# ESP32-Proto2-OSHPARK.net
KiCad netlist of a schematic drawn in EAGLE
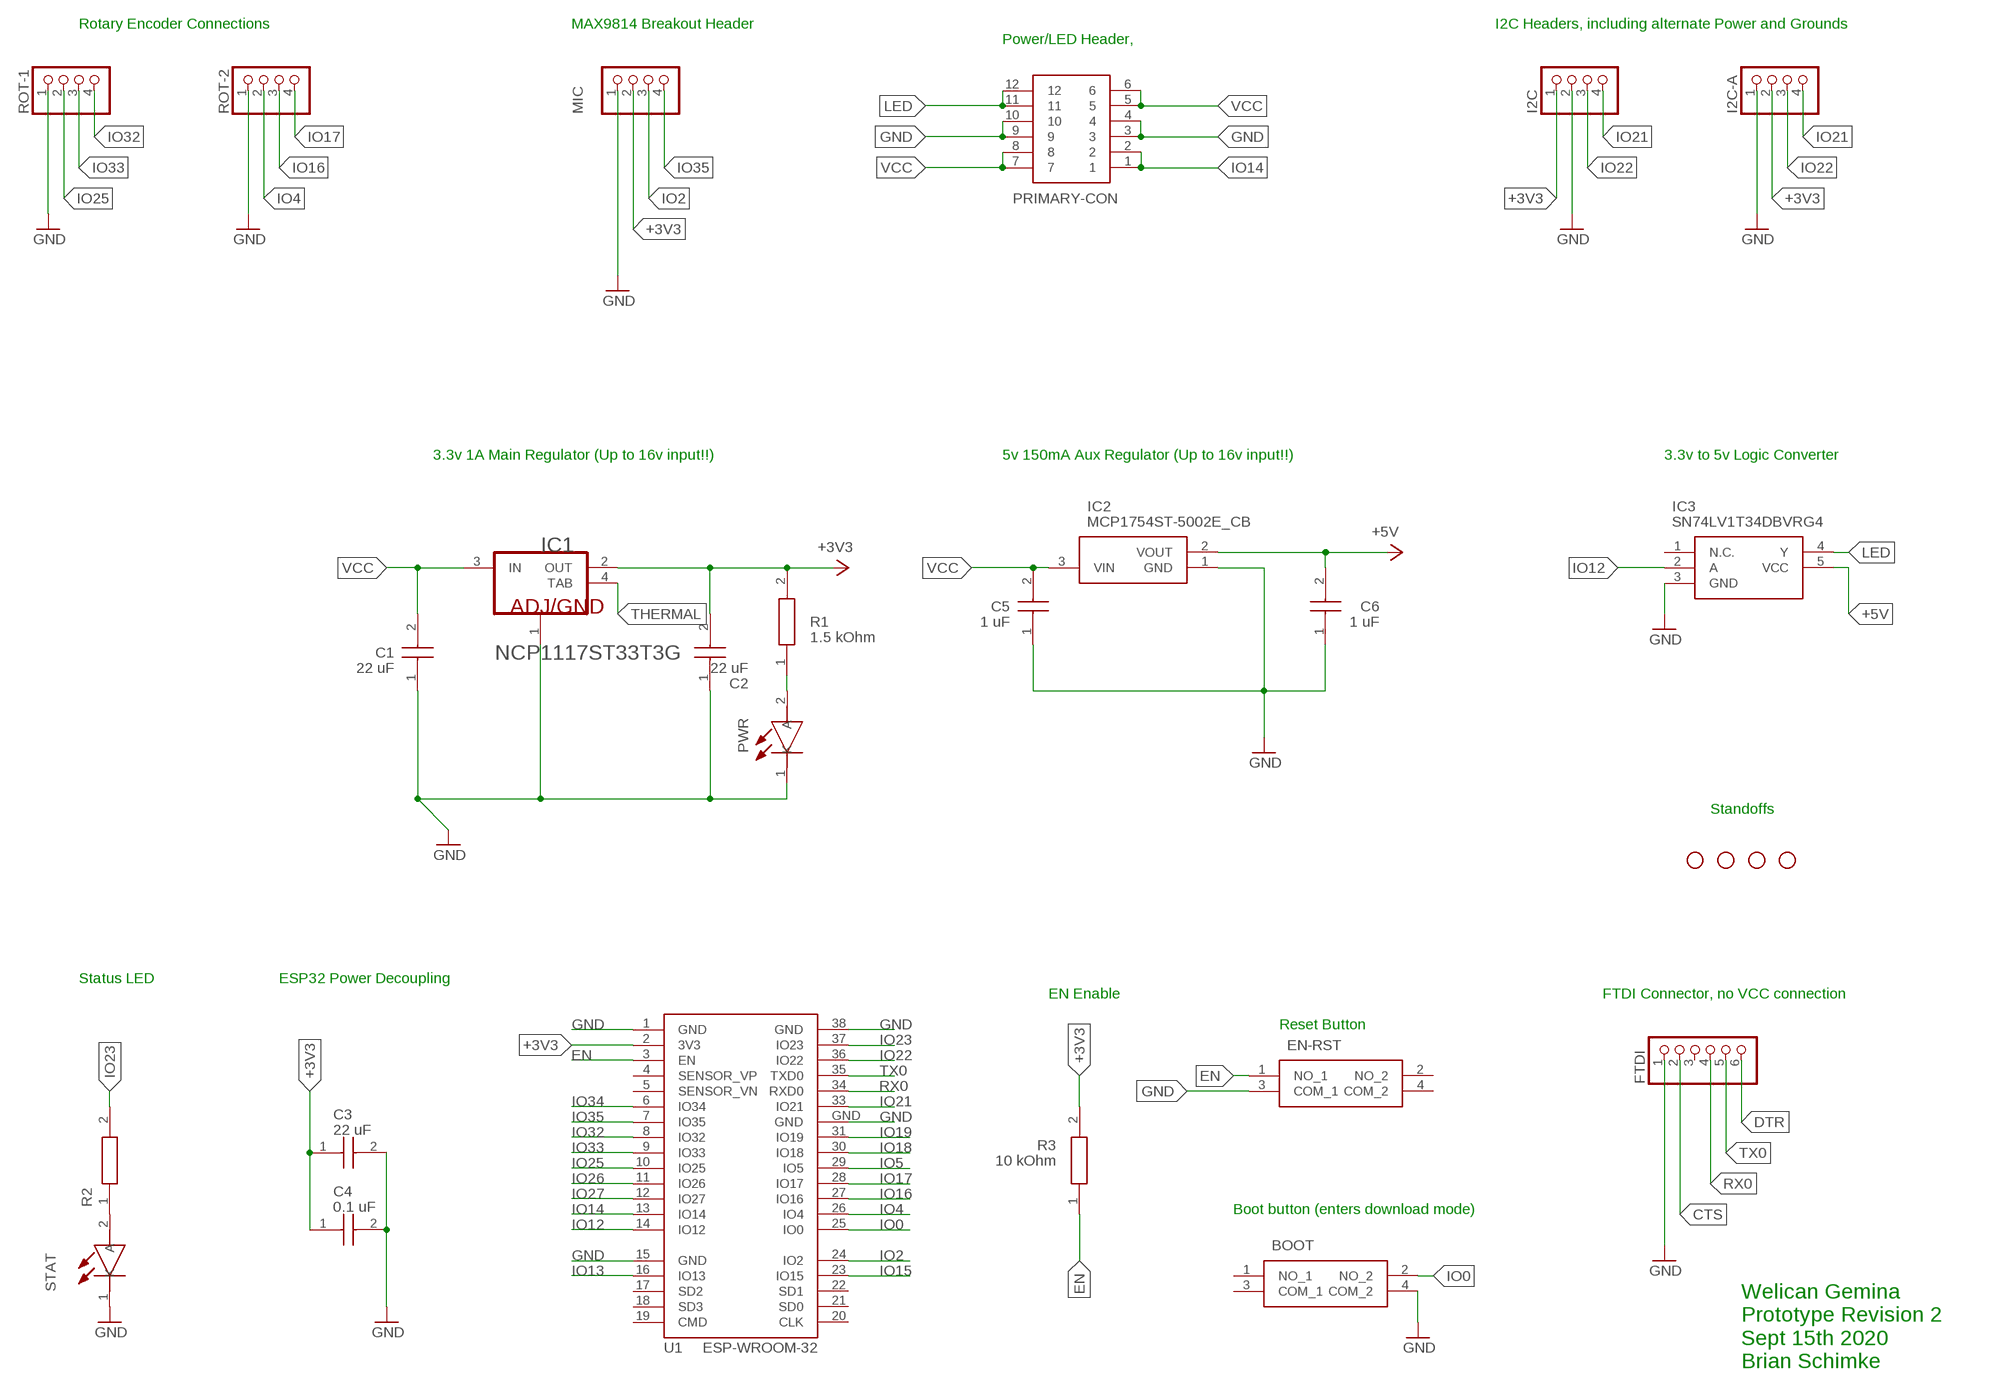
[diagram p0: schematic, sheet 1]

(export (version "E")
  (design (tool "Eeschema 10.0.6"))
  (components
    (comp (ref "BOOT")
      (value "PTS647SK70SMTR2LFS")
      (footprint "eagle-import:PTS647SK70SMTR2LFS")
      (fields (field (name "MOUSER_PART_NUMBER") "611-PTS647SK70SMTR2L"))
      (libsource (lib "eagle-import") (part "PTS647SK70SMTR2LFS"))
    )
    (comp (ref "C1")
      (value "22 uF")
      (footprint "eagle-import:CAPC3216X180N")
      (fields
        (field (name "MANUFACTURER_PART_NUMBER") "C1206C226M4PACTU")
        (field (name "MOUSER_PART_NUMBER") "80-C1206C226M4P")
      )
      (libsource (lib "eagle-import") (part "C1206C226M4PACTU"))
    )
    (comp (ref "C2")
      (value "22 uF")
      (footprint "eagle-import:CAPC3216X180N")
      (fields
        (field (name "MANUFACTURER_PART_NUMBER") "C1206C226M4PACTU")
        (field (name "MOUSER_PART_NUMBER") "80-C1206C226M4P")
      )
      (libsource (lib "eagle-import") (part "C1206C226M4PACTU"))
    )
    (comp (ref "C3")
      (value "22 uF")
      (footprint "eagle-import:CAPC3216X180N")
      (fields
        (field (name "MANUFACTURER_PART_NUMBER") "C1206C226M4PACTU")
        (field (name "MOUSER_PART_NUMBER") "80-C1206C226M4P")
      )
      (libsource (lib "eagle-import") (part "C1206C226M4PACTU"))
    )
    (comp (ref "C4")
      (value "0.1 uF")
      (footprint "eagle-import:CAPC3216X180N")
      (fields
        (field (name "MANUFACTURER_PART_NUMBER") "C1206C226M4PACTU")
        (field (name "MOUSER_PART_NUMBER") "80-C1206C226M4P")
      )
      (libsource (lib "eagle-import") (part "C1206C226M4PACTU"))
    )
    (comp (ref "C5")
      (value "1 uF")
      (footprint "eagle-import:CAPC3216X180N")
      (fields
        (field (name "MANUFACTURER_PART_NUMBER") "C1206C226M4PACTU")
        (field (name "MOUSER_PART_NUMBER") "80-C1206C226M4P")
      )
      (libsource (lib "eagle-import") (part "C1206C226M4PACTU"))
    )
    (comp (ref "C6")
      (value "1 uF")
      (footprint "eagle-import:CAPC3216X180N")
      (fields
        (field (name "MANUFACTURER_PART_NUMBER") "C1206C226M4PACTU")
        (field (name "MOUSER_PART_NUMBER") "80-C1206C226M4P")
      )
      (libsource (lib "eagle-import") (part "C1206C226M4PACTU"))
    )
    (comp (ref "EN-RST")
      (value "PTS647SK70SMTR2LFS")
      (footprint "eagle-import:PTS647SK70SMTR2LFS")
      (fields (field (name "MOUSER_PART_NUMBER") "611-PTS647SK70SMTR2L"))
      (libsource (lib "eagle-import") (part "PTS647SK70SMTR2LFS"))
    )
    (comp (ref "FTDI")
      (value "PINHD-1X6")
      (footprint "eagle-import:1X06")
      (libsource (lib "eagle-import") (part "PINHD-1X6"))
    )
    (comp (ref "H1")
      (value "STAND-OFF")
      (footprint "eagle-import:STAND-OFF")
      (libsource (lib "eagle-import") (part "STAND-OFF"))
    )
    (comp (ref "H2")
      (value "STAND-OFF")
      (footprint "eagle-import:STAND-OFF")
      (libsource (lib "eagle-import") (part "STAND-OFF"))
    )
    (comp (ref "H3")
      (value "STAND-OFF")
      (footprint "eagle-import:STAND-OFF")
      (libsource (lib "eagle-import") (part "STAND-OFF"))
    )
    (comp (ref "H4")
      (value "STAND-OFF")
      (footprint "eagle-import:STAND-OFF")
      (libsource (lib "eagle-import") (part "STAND-OFF"))
    )
    (comp (ref "I2C")
      (value "PINHD-1X4")
      (footprint "eagle-import:1X04")
      (libsource (lib "eagle-import") (part "PINHD-1X4"))
    )
    (comp (ref "I2C-A")
      (value "PINHD-1X4")
      (footprint "eagle-import:1X04")
      (libsource (lib "eagle-import") (part "PINHD-1X4"))
    )
    (comp (ref "IC1")
      (value "ON_SEMICONDUCTOR_NCP1117ST33T3GON_SEMICONDUCTOR_NCP1117ST33T3G_0_0")
      (footprint "eagle-import:ON_SEMICONDUCTOR_NCP1117ST33T3G_0")
      (fields
        (field (name "MF") "ON Semiconductor")
        (field (name "MPN") "NCP1117ST33T3G")
        (field (name "TOLERANCE") "1%")
      )
      (libsource (lib "eagle-import") (part "ON_SEMICONDUCTOR_NCP1117ST33T3GON_SEMICONDUCTOR_NCP1117ST33T3G_0_0"))
    )
    (comp (ref "IC2")
      (value "MCP1754ST-5002E_CB")
      (footprint "eagle-import:SOT95P255X145-3N")
      (fields
        (field (name "MANUFACTURER_PART_NUMBER") "MCP1754ST-5002E/CB")
        (field (name "MOUSER_PART_NUMBER") "579-MCP1754T-5002ECB")
      )
      (libsource (lib "eagle-import") (part "MCP1754ST-5002E_CB"))
    )
    (comp (ref "IC3")
      (value "SN74LV1T34DBVRG4")
      (footprint "eagle-import:SOT95P280X145-5N")
      (fields (field (name "MOUSER_PART_NUMBER") "595-SN74LV1T34DBVRG4"))
      (libsource (lib "eagle-import") (part "SN74LV1T34DBVRG4"))
    )
    (comp (ref "MIC")
      (value "PINHD-1X4")
      (footprint "eagle-import:1X04")
      (libsource (lib "eagle-import") (part "PINHD-1X4"))
    )
    (comp (ref "PRIMARY-CON")
      (value "1-2834015-6")
      (footprint "eagle-import:SHDR12W90P508X254_2X6_1824X128")
      (fields (field (name "MOUSER_PART_NUMBER") "571-1-2834015-6"))
      (libsource (lib "eagle-import") (part "1-2834015-6"))
    )
    (comp (ref "PWR")
      (value "150120AS75000")
      (footprint "eagle-import:LEDSC320X160X78-2N")
      (fields (field (name "MOUSER_PART_NUMBER") "710-150120AS75000"))
      (libsource (lib "eagle-import") (part "150120AS75000"))
    )
    (comp (ref "R1")
      (value "1.5 kOhm")
      (footprint "eagle-import:RESC3216X60N")
      (fields
        (field (name "MANUFACTURER_PART_NUMBER") "CRCW12061K00FKEB")
        (field (name "MOUSER_PART_NUMBER") "71-CRCW12061K00FKEB")
      )
      (libsource (lib "eagle-import") (part "CRCW12061K00FKEB"))
    )
    (comp (ref "R2")
      (value "CRCW12061K00FKEB")
      (footprint "eagle-import:RESC3216X60N")
      (fields (field (name "MOUSER_PART_NUMBER") "71-CRCW12061K00FKEB"))
      (libsource (lib "eagle-import") (part "CRCW12061K00FKEB"))
    )
    (comp (ref "R3")
      (value "10 kOhm")
      (footprint "eagle-import:RESC3216X60N")
      (fields
        (field (name "MANUFACTURER_PART_NUMBER") "CRCW12061K00FKEB")
        (field (name "MOUSER_PART_NUMBER") "71-CRCW12061K00FKEB")
      )
      (libsource (lib "eagle-import") (part "CRCW12061K00FKEB"))
    )
    (comp (ref "ROT-1")
      (value "PINHD-1X4")
      (footprint "eagle-import:1X04")
      (libsource (lib "eagle-import") (part "PINHD-1X4"))
    )
    (comp (ref "ROT-2")
      (value "PINHD-1X4")
      (footprint "eagle-import:1X04")
      (libsource (lib "eagle-import") (part "PINHD-1X4"))
    )
    (comp (ref "STAT")
      (value "150120AS75000")
      (footprint "eagle-import:LEDSC320X160X78-2N")
      (fields (field (name "MOUSER_PART_NUMBER") "710-150120AS75000"))
      (libsource (lib "eagle-import") (part "150120AS75000"))
    )
    (comp (ref "U1")
      (value "ESP-WROOM-32")
      (footprint "eagle-import:ESP-WROOM-32")
      (libsource (lib "eagle-import") (part "ESP-WROOM-32"))
    )
  )
  (nets
    (net (code "1") (name "+3V3") (class "Default")
      (node (ref "C2") (pin "2") (pinfunction "2_2") (pintype "bidirectional"))
      (node (ref "C3") (pin "1") (pinfunction "1_1") (pintype "bidirectional"))
      (node (ref "C4") (pin "1") (pinfunction "1_1") (pintype "bidirectional"))
      (node (ref "I2C") (pin "1") (pinfunction "1_1") (pintype "passive"))
      (node (ref "I2C-A") (pin "2") (pinfunction "2_2") (pintype "passive"))
      (node (ref "IC1") (pin "2") (pinfunction "OUT_2") (pintype "power_in"))
      (node (ref "MIC") (pin "2") (pinfunction "2_2") (pintype "passive"))
      (node (ref "R1") (pin "2") (pinfunction "2_2") (pintype "bidirectional"))
      (node (ref "R3") (pin "2") (pinfunction "2_2") (pintype "bidirectional"))
      (node (ref "U1") (pin "2") (pinfunction "3V3_2") (pintype "power_in"))
    )
    (net (code "2") (name "+5V") (class "Default")
      (node (ref "C6") (pin "2") (pinfunction "2_2") (pintype "bidirectional"))
      (node (ref "IC2") (pin "2") (pinfunction "VOUT_2") (pintype "bidirectional"))
      (node (ref "IC3") (pin "5") (pinfunction "VCC_5") (pintype "bidirectional"))
    )
    (net (code "3") (name "/IO5") (class "Default")
      (node (ref "U1") (pin "29") (pinfunction "IO5_29") (pintype "bidirectional"))
    )
    (net (code "4") (name "/IO13") (class "Default")
      (node (ref "U1") (pin "16") (pinfunction "IO13_16") (pintype "bidirectional"))
    )
    (net (code "5") (name "/IO15") (class "Default")
      (node (ref "U1") (pin "23") (pinfunction "IO15_23") (pintype "bidirectional"))
    )
    (net (code "6") (name "/IO18") (class "Default")
      (node (ref "U1") (pin "30") (pinfunction "IO18_30") (pintype "bidirectional"))
    )
    (net (code "7") (name "/IO19") (class "Default")
      (node (ref "U1") (pin "31") (pinfunction "IO19_31") (pintype "bidirectional"))
    )
    (net (code "8") (name "/IO26") (class "Default")
      (node (ref "U1") (pin "11") (pinfunction "IO26_11") (pintype "bidirectional"))
    )
    (net (code "9") (name "/IO27") (class "Default")
      (node (ref "U1") (pin "12") (pinfunction "IO27_12") (pintype "bidirectional"))
    )
    (net (code "10") (name "/IO34") (class "Default")
      (node (ref "U1") (pin "6") (pinfunction "IO34_6") (pintype "bidirectional"))
    )
    (net (code "11") (name "CTS") (class "Default")
      (node (ref "FTDI") (pin "2") (pinfunction "2_2") (pintype "passive"))
    )
    (net (code "12") (name "DTR") (class "Default")
      (node (ref "FTDI") (pin "6") (pinfunction "6_6") (pintype "passive"))
    )
    (net (code "13") (name "EN") (class "Default")
      (node (ref "EN-RST") (pin "1") (pinfunction "NO_1_1") (pintype "bidirectional"))
      (node (ref "R3") (pin "1") (pinfunction "1_1") (pintype "bidirectional"))
      (node (ref "U1") (pin "3") (pinfunction "EN_3") (pintype "input"))
    )
    (net (code "14") (name "GND") (class "Default")
      (node (ref "BOOT") (pin "4") (pinfunction "COM_2_4") (pintype "bidirectional"))
      (node (ref "C1") (pin "1") (pinfunction "1_1") (pintype "bidirectional"))
      (node (ref "C2") (pin "1") (pinfunction "1_1") (pintype "bidirectional"))
      (node (ref "C3") (pin "2") (pinfunction "2_2") (pintype "bidirectional"))
      (node (ref "C4") (pin "2") (pinfunction "2_2") (pintype "bidirectional"))
      (node (ref "C5") (pin "1") (pinfunction "1_1") (pintype "bidirectional"))
      (node (ref "C6") (pin "1") (pinfunction "1_1") (pintype "bidirectional"))
      (node (ref "EN-RST") (pin "3") (pinfunction "COM_1_3") (pintype "bidirectional"))
      (node (ref "FTDI") (pin "1") (pinfunction "1_1") (pintype "passive"))
      (node (ref "I2C") (pin "2") (pinfunction "2_2") (pintype "passive"))
      (node (ref "I2C-A") (pin "1") (pinfunction "1_1") (pintype "passive"))
      (node (ref "IC1") (pin "1") (pinfunction "ADJ/GND_1") (pintype "passive"))
      (node (ref "IC2") (pin "1") (pinfunction "GND_1") (pintype "bidirectional"))
      (node (ref "IC3") (pin "3") (pinfunction "GND_3") (pintype "bidirectional"))
      (node (ref "MIC") (pin "1") (pinfunction "1_1") (pintype "passive"))
      (node (ref "PRIMARY-CON") (pin "10") (pinfunction "10_10") (pintype "bidirectional"))
      (node (ref "PRIMARY-CON") (pin "3") (pinfunction "3_3") (pintype "bidirectional"))
      (node (ref "PRIMARY-CON") (pin "4") (pinfunction "4_4") (pintype "bidirectional"))
      (node (ref "PRIMARY-CON") (pin "9") (pinfunction "9_9") (pintype "bidirectional"))
      (node (ref "PWR") (pin "1") (pinfunction "K_1") (pintype "bidirectional"))
      (node (ref "ROT-1") (pin "1") (pinfunction "1_1") (pintype "passive"))
      (node (ref "ROT-2") (pin "1") (pinfunction "1_1") (pintype "passive"))
      (node (ref "STAT") (pin "1") (pinfunction "K_1") (pintype "bidirectional"))
      (node (ref "U1") (pin "1") (pinfunction "GND_1") (pintype "power_in"))
      (node (ref "U1") (pin "15") (pinfunction "GND_15") (pintype "power_in"))
      (node (ref "U1") (pin "38") (pinfunction "GND_38") (pintype "power_in"))
      (node (ref "U1") (pin "GND") (pinfunction "GND_GND") (pintype "power_in"))
    )
    (net (code "15") (name "IO0") (class "Default")
      (node (ref "BOOT") (pin "2") (pinfunction "NO_2_2") (pintype "bidirectional"))
      (node (ref "U1") (pin "25") (pinfunction "IO0_25") (pintype "bidirectional"))
    )
    (net (code "16") (name "IO2") (class "Default")
      (node (ref "MIC") (pin "3") (pinfunction "3_3") (pintype "passive"))
      (node (ref "U1") (pin "24") (pinfunction "IO2_24") (pintype "bidirectional"))
    )
    (net (code "17") (name "IO4") (class "Default")
      (node (ref "ROT-2") (pin "2") (pinfunction "2_2") (pintype "passive"))
      (node (ref "U1") (pin "26") (pinfunction "IO4_26") (pintype "bidirectional"))
    )
    (net (code "18") (name "IO12") (class "Default")
      (node (ref "IC3") (pin "2") (pinfunction "A_2") (pintype "bidirectional"))
      (node (ref "U1") (pin "14") (pinfunction "IO12_14") (pintype "bidirectional"))
    )
    (net (code "19") (name "IO14") (class "Default")
      (node (ref "PRIMARY-CON") (pin "1") (pinfunction "1_1") (pintype "bidirectional"))
      (node (ref "PRIMARY-CON") (pin "2") (pinfunction "2_2") (pintype "bidirectional"))
      (node (ref "U1") (pin "13") (pinfunction "IO14_13") (pintype "bidirectional"))
    )
    (net (code "20") (name "IO16") (class "Default")
      (node (ref "ROT-2") (pin "3") (pinfunction "3_3") (pintype "passive"))
      (node (ref "U1") (pin "27") (pinfunction "IO16_27") (pintype "bidirectional"))
    )
    (net (code "21") (name "IO17") (class "Default")
      (node (ref "ROT-2") (pin "4") (pinfunction "4_4") (pintype "passive"))
      (node (ref "U1") (pin "28") (pinfunction "IO17_28") (pintype "bidirectional"))
    )
    (net (code "22") (name "IO21") (class "Default")
      (node (ref "I2C") (pin "4") (pinfunction "4_4") (pintype "passive"))
      (node (ref "I2C-A") (pin "4") (pinfunction "4_4") (pintype "passive"))
      (node (ref "U1") (pin "33") (pinfunction "IO21_33") (pintype "bidirectional"))
    )
    (net (code "23") (name "IO22") (class "Default")
      (node (ref "I2C") (pin "3") (pinfunction "3_3") (pintype "passive"))
      (node (ref "I2C-A") (pin "3") (pinfunction "3_3") (pintype "passive"))
      (node (ref "U1") (pin "36") (pinfunction "IO22_36") (pintype "bidirectional"))
    )
    (net (code "24") (name "IO23") (class "Default")
      (node (ref "R2") (pin "2") (pinfunction "2_2") (pintype "bidirectional"))
      (node (ref "U1") (pin "37") (pinfunction "IO23_37") (pintype "bidirectional"))
    )
    (net (code "25") (name "IO25") (class "Default")
      (node (ref "ROT-1") (pin "2") (pinfunction "2_2") (pintype "passive"))
      (node (ref "U1") (pin "10") (pinfunction "IO25_10") (pintype "bidirectional"))
    )
    (net (code "26") (name "IO32") (class "Default")
      (node (ref "ROT-1") (pin "4") (pinfunction "4_4") (pintype "passive"))
      (node (ref "U1") (pin "8") (pinfunction "IO32_8") (pintype "bidirectional"))
    )
    (net (code "27") (name "IO33") (class "Default")
      (node (ref "ROT-1") (pin "3") (pinfunction "3_3") (pintype "passive"))
      (node (ref "U1") (pin "9") (pinfunction "IO33_9") (pintype "bidirectional"))
    )
    (net (code "28") (name "IO35") (class "Default")
      (node (ref "MIC") (pin "4") (pinfunction "4_4") (pintype "passive"))
      (node (ref "U1") (pin "7") (pinfunction "IO35_7") (pintype "bidirectional"))
    )
    (net (code "29") (name "LED") (class "Default")
      (node (ref "IC3") (pin "4") (pinfunction "Y_4") (pintype "bidirectional"))
      (node (ref "PRIMARY-CON") (pin "11") (pinfunction "11_11") (pintype "bidirectional"))
      (node (ref "PRIMARY-CON") (pin "12") (pinfunction "12_12") (pintype "bidirectional"))
    )
    (net (code "30") (name "Net-(PWR-A)") (class "Default")
      (node (ref "PWR") (pin "2") (pinfunction "A_2") (pintype "bidirectional"))
      (node (ref "R1") (pin "1") (pinfunction "1_1") (pintype "bidirectional"))
    )
    (net (code "31") (name "Net-(STAT-A)") (class "Default")
      (node (ref "R2") (pin "1") (pinfunction "1_1") (pintype "bidirectional"))
      (node (ref "STAT") (pin "2") (pinfunction "A_2") (pintype "bidirectional"))
    )
    (net (code "32") (name "RX0") (class "Default")
      (node (ref "FTDI") (pin "4") (pinfunction "4_4") (pintype "passive"))
      (node (ref "U1") (pin "34") (pinfunction "RXD0_34") (pintype "bidirectional"))
    )
    (net (code "33") (name "THERMAL") (class "Default")
      (node (ref "IC1") (pin "4") (pinfunction "TAB_4") (pintype "passive"))
    )
    (net (code "34") (name "TX0") (class "Default")
      (node (ref "FTDI") (pin "5") (pinfunction "5_5") (pintype "passive"))
      (node (ref "U1") (pin "35") (pinfunction "TXD0_35") (pintype "bidirectional"))
    )
    (net (code "35") (name "VCC") (class "Default")
      (node (ref "C1") (pin "2") (pinfunction "2_2") (pintype "bidirectional"))
      (node (ref "C5") (pin "2") (pinfunction "2_2") (pintype "bidirectional"))
      (node (ref "IC1") (pin "3") (pinfunction "IN_3") (pintype "power_in"))
      (node (ref "IC2") (pin "3") (pinfunction "VIN_3") (pintype "bidirectional"))
      (node (ref "PRIMARY-CON") (pin "5") (pinfunction "5_5") (pintype "bidirectional"))
      (node (ref "PRIMARY-CON") (pin "6") (pinfunction "6_6") (pintype "bidirectional"))
      (node (ref "PRIMARY-CON") (pin "7") (pinfunction "7_7") (pintype "bidirectional"))
      (node (ref "PRIMARY-CON") (pin "8") (pinfunction "8_8") (pintype "bidirectional"))
    )
    (net (code "36") (name "unconnected-(BOOT-COM_1-Pad3)") (class "Default")
      (node (ref "BOOT") (pin "3") (pinfunction "COM_1_3") (pintype "bidirectional"))
    )
    (net (code "37") (name "unconnected-(BOOT-NO_1-Pad1)") (class "Default")
      (node (ref "BOOT") (pin "1") (pinfunction "NO_1_1") (pintype "bidirectional"))
    )
    (net (code "38") (name "unconnected-(EN-RST-COM_2-Pad4)") (class "Default")
      (node (ref "EN-RST") (pin "4") (pinfunction "COM_2_4") (pintype "bidirectional"))
    )
    (net (code "39") (name "unconnected-(EN-RST-NO_2-Pad2)") (class "Default")
      (node (ref "EN-RST") (pin "2") (pinfunction "NO_2_2") (pintype "bidirectional"))
    )
    (net (code "40") (name "unconnected-(FTDI-Pad3)") (class "Default")
      (node (ref "FTDI") (pin "3") (pinfunction "3_3") (pintype "passive"))
    )
    (net (code "41") (name "unconnected-(IC3-N.C.-Pad1)") (class "Default")
      (node (ref "IC3") (pin "1") (pinfunction "N.C._1") (pintype "no_connect"))
    )
    (net (code "42") (name "unconnected-(U1-CLK-Pad20)") (class "Default")
      (node (ref "U1") (pin "20") (pinfunction "CLK_20") (pintype "bidirectional"))
    )
    (net (code "43") (name "unconnected-(U1-CMD-Pad19)") (class "Default")
      (node (ref "U1") (pin "19") (pinfunction "CMD_19") (pintype "bidirectional"))
    )
    (net (code "44") (name "unconnected-(U1-SD0-Pad21)") (class "Default")
      (node (ref "U1") (pin "21") (pinfunction "SD0_21") (pintype "bidirectional"))
    )
    (net (code "45") (name "unconnected-(U1-SD1-Pad22)") (class "Default")
      (node (ref "U1") (pin "22") (pinfunction "SD1_22") (pintype "bidirectional"))
    )
    (net (code "46") (name "unconnected-(U1-SD2-Pad17)") (class "Default")
      (node (ref "U1") (pin "17") (pinfunction "SD2_17") (pintype "bidirectional"))
    )
    (net (code "47") (name "unconnected-(U1-SD3-Pad18)") (class "Default")
      (node (ref "U1") (pin "18") (pinfunction "SD3_18") (pintype "bidirectional"))
    )
    (net (code "48") (name "unconnected-(U1-SENSOR_VN-Pad5)") (class "Default")
      (node (ref "U1") (pin "5") (pinfunction "SENSOR_VN_5") (pintype "bidirectional"))
    )
    (net (code "49") (name "unconnected-(U1-SENSOR_VP-Pad4)") (class "Default")
      (node (ref "U1") (pin "4") (pinfunction "SENSOR_VP_4") (pintype "bidirectional"))
    )
  )
)
